# Clock_Input.net
KiCad netlist of a schematic drawn in Altium Designer
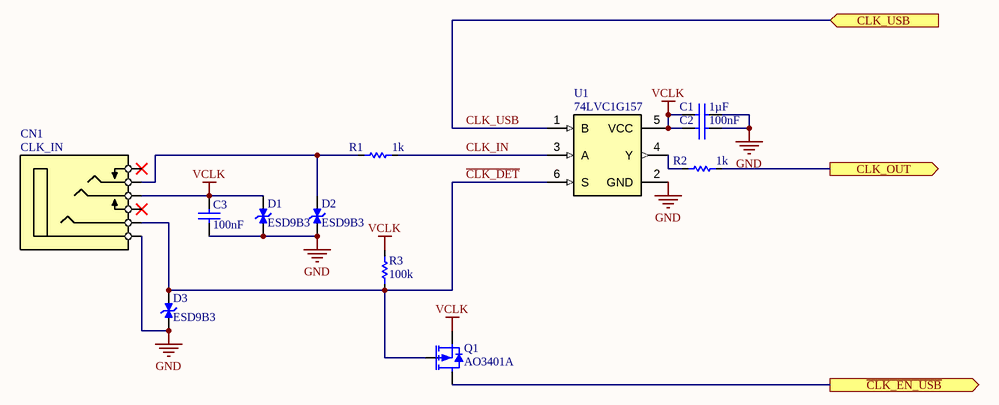
[diagram p0: Clock Input.SchDoc]

(export (version "E")
  (design (tool "Eeschema 10.0.6"))
  (components
    (comp (ref "C1")
      (value "1µF")
      (footprint "CAP_CHIP_0603")
      (description "0603 Multilayer Ceramic Capacitors MLCC")
      (fields (field (name "PARTNUMBER") "CL10A105KB8NNNC") (field (name "TOLERANCE") "10%"))
      (libsource (lib "Sainsbury Wellcome Centre") (part "Cap"))
    )
    (comp (ref "C2")
      (value "100nF")
      (footprint "CAP_CHIP_0603")
      (description "0603 Multilayer Ceramic Capacitors MLCC")
      (fields (field (name "TOLERANCE") "10%") (field (name "PARTNUMBER") "CC0603KRX7R9BB104"))
      (libsource (lib "Sainsbury Wellcome Centre") (part "Cap"))
    )
    (comp (ref "C3")
      (value "100nF")
      (footprint "CAP_CHIP_0603")
      (description "0603 Multilayer Ceramic Capacitors MLCC")
      (fields (field (name "TOLERANCE") "10%") (field (name "PARTNUMBER") "CC0603KRX7R9BB104"))
      (libsource (lib "Sainsbury Wellcome Centre") (part "Cap"))
    )
    (comp (ref "CN1")
      (value "CLK_IN")
      (footprint "PJ-316A")
      (description "3.5mm headphone jack 235℃ 30V 500mA SMD Audio Connector")
      (fields (field (name "PARTNUMBER") "PJ-316A-6A"))
      (libsource (lib "Sainsbury Wellcome Centre") (part "PJ-316A"))
    )
    (comp (ref "D1")
      (value "ESD9B3")
      (footprint "SOD923")
      (description "ESD9B3.3ST5G, Bi-Directional TVS Diode, 300mW, 2-Pin SOD-923")
      (fields (field (name "PARTNUMBER") "ESD9B3.3ST5G"))
      (libsource (lib "Sainsbury Wellcome Centre") (part "TVS-2P-BI"))
    )
    (comp (ref "D2")
      (value "ESD9B3")
      (footprint "SOD923")
      (description "ESD9B3.3ST5G, Bi-Directional TVS Diode, 300mW, 2-Pin SOD-923")
      (fields (field (name "PARTNUMBER") "ESD9B3.3ST5G"))
      (libsource (lib "Sainsbury Wellcome Centre") (part "TVS-2P-BI"))
    )
    (comp (ref "D3")
      (value "ESD9B3")
      (footprint "SOD923")
      (description "ESD9B3.3ST5G, Bi-Directional TVS Diode, 300mW, 2-Pin SOD-923")
      (fields (field (name "PARTNUMBER") "ESD9B3.3ST5G"))
      (libsource (lib "Sainsbury Wellcome Centre") (part "TVS-2P-BI"))
    )
    (comp (ref "Q1")
      (value "AO3401A")
      (footprint "SOT23")
      (description "30V 4A 44mΩ@10V,4.3A 1.4W 1.3V@250uA 1 PChannel SOT-23-3L MOSFETs")
      (fields (field (name "PARTNUMBER") "AO3401A"))
      (libsource (lib "Sainsbury Wellcome Centre") (part "PMOS"))
    )
    (comp (ref "R1")
      (value "1k")
      (footprint "RES_CHIP_0603")
      (description "100mW Thick Film Resistors 75V ±100ppm/℃ ±1% 0603 Chip Resistor")
      (fields (field (name "TOLERANCE") "1%") (field (name "PARTNUMBER") "0603WAF1001T5E"))
      (libsource (lib "Sainsbury Wellcome Centre") (part "Res"))
    )
    (comp (ref "R2")
      (value "1k")
      (footprint "RES_CHIP_0603")
      (description "100mW Thick Film Resistors 75V ±100ppm/℃ ±1% 0603 Chip Resistor")
      (fields (field (name "TOLERANCE") "1%") (field (name "PARTNUMBER") "0603WAF1001T5E"))
      (libsource (lib "Sainsbury Wellcome Centre") (part "Res"))
    )
    (comp (ref "R3")
      (value "100k")
      (footprint "RES_CHIP_0603")
      (description "100mW Thick Film Resistors 75V ±100ppm/℃ ±1% 0603 Chip Resistor")
      (fields (field (name "PARTNUMBER") "0603WAF1003T5E") (field (name "TOLERANCE") "1%"))
      (libsource (lib "Sainsbury Wellcome Centre") (part "Res"))
    )
    (comp (ref "U1")
      (value "74LVC1G157")
      (footprint "SOT363")
      (description "Encoders, Decoders, Multiplexers & Demultiplexers 74LVC1G157GV-Q100/SC-74/REEL 7")
      (fields (field (name "PARTNUMBER") "74LVC1G157GV"))
      (libsource (lib "Sainsbury Wellcome Centre") (part "74LVC1G157"))
    )
  )
  (nets
    (net (code "1") (name "/CLK_IN") (class "Default")
      (node (ref "R1") (pin "1") (pinfunction "1_1") (pintype "passive"))
      (node (ref "U1") (pin "3") (pinfunction "A_3") (pintype "input"))
    )
    (net (code "2") (name "/CLK_OUT") (class "Default")
      (node (ref "R2") (pin "1") (pinfunction "1_1") (pintype "passive"))
    )
    (net (code "3") (name "/CLK_USB") (class "Default")
      (node (ref "U1") (pin "1") (pinfunction "B_1") (pintype "input"))
    )
    (net (code "4") (name "/~{CLK_DET}") (class "Default")
      (node (ref "CN1") (pin "4") (pinfunction "RR_4") (pintype "passive"))
      (node (ref "D3") (pin "2") (pinfunction "A_2") (pintype "passive"))
      (node (ref "Q1") (pin "1") (pinfunction "G_1") (pintype "passive"))
      (node (ref "R3") (pin "1") (pinfunction "1_1") (pintype "passive"))
      (node (ref "U1") (pin "6") (pinfunction "S_6") (pintype "input"))
    )
    (net (code "5") (name "/~{CLK_EN_USB}") (class "Default")
      (node (ref "Q1") (pin "3") (pinfunction "D_3") (pintype "passive"))
    )
    (net (code "6") (name "GND") (class "Default")
      (node (ref "C1") (pin "1") (pinfunction "1_1") (pintype "passive"))
      (node (ref "C2") (pin "1") (pinfunction "1_1") (pintype "passive"))
      (node (ref "C3") (pin "1") (pinfunction "1_1") (pintype "passive"))
      (node (ref "CN1") (pin "1") (pinfunction "S_1") (pintype "passive"))
      (node (ref "D1") (pin "1") (pinfunction "K_1") (pintype "passive"))
      (node (ref "D2") (pin "1") (pinfunction "K_1") (pintype "passive"))
      (node (ref "D3") (pin "1") (pinfunction "K_1") (pintype "passive"))
      (node (ref "U1") (pin "2") (pinfunction "GND_2") (pintype "power_in"))
    )
    (net (code "7") (name "Net-(CN1-T)") (class "Default")
      (node (ref "CN1") (pin "2") (pinfunction "T_2") (pintype "passive"))
      (node (ref "D2") (pin "2") (pinfunction "A_2") (pintype "passive"))
      (node (ref "R1") (pin "2") (pinfunction "2_2") (pintype "passive"))
    )
    (net (code "8") (name "Net-(U1-Y)") (class "Default")
      (node (ref "R2") (pin "2") (pinfunction "2_2") (pintype "passive"))
      (node (ref "U1") (pin "4") (pinfunction "Y_4") (pintype "output"))
    )
    (net (code "9") (name "VCLK") (class "Default")
      (node (ref "C1") (pin "2") (pinfunction "2_2") (pintype "passive"))
      (node (ref "C2") (pin "2") (pinfunction "2_2") (pintype "passive"))
      (node (ref "C3") (pin "2") (pinfunction "2_2") (pintype "passive"))
      (node (ref "CN1") (pin "3") (pinfunction "R_3") (pintype "passive"))
      (node (ref "D1") (pin "2") (pinfunction "A_2") (pintype "passive"))
      (node (ref "Q1") (pin "2") (pinfunction "S_2") (pintype "passive"))
      (node (ref "R3") (pin "2") (pinfunction "2_2") (pintype "passive"))
      (node (ref "U1") (pin "5") (pinfunction "VCC_5") (pintype "power_in"))
    )
    (net (code "10") (name "unconnected-(CN1-RS-Pad6)") (class "Default")
      (node (ref "CN1") (pin "6") (pinfunction "RS_6") (pintype "passive+no_connect"))
    )
    (net (code "11") (name "unconnected-(CN1-TS-Pad5)") (class "Default")
      (node (ref "CN1") (pin "5") (pinfunction "TS_5") (pintype "passive+no_connect"))
    )
  )
)
